# xiao_mx.net
KiCad netlist of a schematic drawn in EAGLE
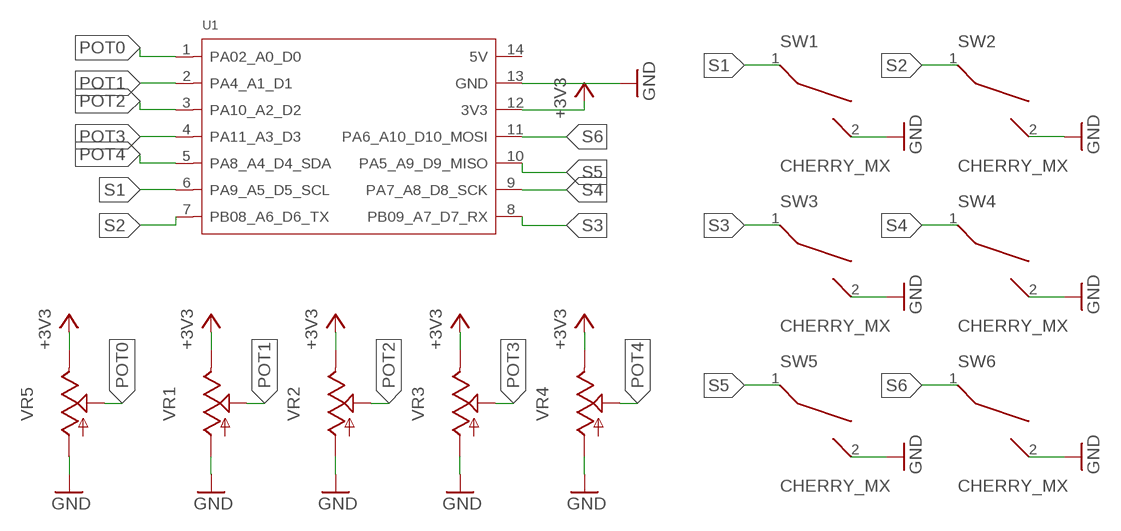
[diagram p0: schematic, sheet 1]

(export (version "E")
  (design (tool "Eeschema 10.0.6"))
  (components
    (comp (ref "SW1")
      (value "CHERRY_MX")
      (footprint "eagle-import:MX1A-XXNN")
      (libsource (lib "eagle-import") (part "CHERRY_MX"))
    )
    (comp (ref "SW2")
      (value "CHERRY_MX")
      (footprint "eagle-import:MX1A-XXNN")
      (libsource (lib "eagle-import") (part "CHERRY_MX"))
    )
    (comp (ref "SW3")
      (value "CHERRY_MX")
      (footprint "eagle-import:MX1A-XXNN")
      (libsource (lib "eagle-import") (part "CHERRY_MX"))
    )
    (comp (ref "SW4")
      (value "CHERRY_MX")
      (footprint "eagle-import:MX1A-XXNN")
      (libsource (lib "eagle-import") (part "CHERRY_MX"))
    )
    (comp (ref "SW5")
      (value "CHERRY_MX")
      (footprint "eagle-import:MX1A-XXNN")
      (libsource (lib "eagle-import") (part "CHERRY_MX"))
    )
    (comp (ref "SW6")
      (value "CHERRY_MX")
      (footprint "eagle-import:MX1A-XXNN")
      (libsource (lib "eagle-import") (part "CHERRY_MX"))
    )
    (comp (ref "U1")
      (value "MOUDLE-SEEEDUINO-XIAO")
      (footprint "eagle-import:MOUDLE14P-2.54-21X17.8MM")
      (libsource (lib "eagle-import") (part "MOUDLE-SEEEDUINO-XIAO"))
    )
    (comp (ref "VR1")
      (value "9MM_SNAP-IN_POT_")
      (footprint "eagle-import:9MM_SNAP-IN_POT")
      (libsource (lib "eagle-import") (part "9MM_SNAP-IN_POT_"))
    )
    (comp (ref "VR2")
      (value "9MM_SNAP-IN_POT_")
      (footprint "eagle-import:9MM_SNAP-IN_POT")
      (libsource (lib "eagle-import") (part "9MM_SNAP-IN_POT_"))
    )
    (comp (ref "VR3")
      (value "9MM_SNAP-IN_POT_")
      (footprint "eagle-import:9MM_SNAP-IN_POT")
      (libsource (lib "eagle-import") (part "9MM_SNAP-IN_POT_"))
    )
    (comp (ref "VR4")
      (value "9MM_SNAP-IN_POT_")
      (footprint "eagle-import:9MM_SNAP-IN_POT")
      (libsource (lib "eagle-import") (part "9MM_SNAP-IN_POT_"))
    )
    (comp (ref "VR5")
      (value "9MM_SNAP-IN_POT_")
      (footprint "eagle-import:9MM_SNAP-IN_POT")
      (libsource (lib "eagle-import") (part "9MM_SNAP-IN_POT_"))
    )
  )
  (nets
    (net (code "1") (name "+3V3") (class "Default")
      (node (ref "U1") (pin "12") (pinfunction "3V3_12") (pintype "bidirectional"))
      (node (ref "VR1") (pin "3") (pinfunction "E_3") (pintype "passive"))
      (node (ref "VR2") (pin "3") (pinfunction "E_3") (pintype "passive"))
      (node (ref "VR3") (pin "3") (pinfunction "E_3") (pintype "passive"))
      (node (ref "VR4") (pin "3") (pinfunction "E_3") (pintype "passive"))
      (node (ref "VR5") (pin "3") (pinfunction "E_3") (pintype "passive"))
    )
    (net (code "2") (name "GND") (class "Default")
      (node (ref "SW1") (pin "2") (pinfunction "2_2") (pintype "passive"))
      (node (ref "SW2") (pin "2") (pinfunction "2_2") (pintype "passive"))
      (node (ref "SW3") (pin "2") (pinfunction "2_2") (pintype "passive"))
      (node (ref "SW4") (pin "2") (pinfunction "2_2") (pintype "passive"))
      (node (ref "SW5") (pin "2") (pinfunction "2_2") (pintype "passive"))
      (node (ref "SW6") (pin "2") (pinfunction "2_2") (pintype "passive"))
      (node (ref "U1") (pin "13") (pinfunction "GND_13") (pintype "bidirectional"))
      (node (ref "VR1") (pin "1") (pinfunction "A_1") (pintype "passive"))
      (node (ref "VR2") (pin "1") (pinfunction "A_1") (pintype "passive"))
      (node (ref "VR3") (pin "1") (pinfunction "A_1") (pintype "passive"))
      (node (ref "VR4") (pin "1") (pinfunction "A_1") (pintype "passive"))
      (node (ref "VR5") (pin "1") (pinfunction "A_1") (pintype "passive"))
    )
    (net (code "3") (name "POT0") (class "Default")
      (node (ref "U1") (pin "1") (pinfunction "PA02_A0_D0_1") (pintype "bidirectional"))
      (node (ref "VR5") (pin "2") (pinfunction "S_2") (pintype "passive"))
    )
    (net (code "4") (name "POT1") (class "Default")
      (node (ref "U1") (pin "2") (pinfunction "PA4_A1_D1_2") (pintype "bidirectional"))
      (node (ref "VR1") (pin "2") (pinfunction "S_2") (pintype "passive"))
    )
    (net (code "5") (name "POT2") (class "Default")
      (node (ref "U1") (pin "3") (pinfunction "PA10_A2_D2_3") (pintype "bidirectional"))
      (node (ref "VR2") (pin "2") (pinfunction "S_2") (pintype "passive"))
    )
    (net (code "6") (name "POT3") (class "Default")
      (node (ref "U1") (pin "4") (pinfunction "PA11_A3_D3_4") (pintype "bidirectional"))
      (node (ref "VR3") (pin "2") (pinfunction "S_2") (pintype "passive"))
    )
    (net (code "7") (name "POT4") (class "Default")
      (node (ref "U1") (pin "5") (pinfunction "PA8_A4_D4_SDA_5") (pintype "bidirectional"))
      (node (ref "VR4") (pin "2") (pinfunction "S_2") (pintype "passive"))
    )
    (net (code "8") (name "S1") (class "Default")
      (node (ref "SW1") (pin "1") (pinfunction "1_1") (pintype "passive"))
      (node (ref "U1") (pin "6") (pinfunction "PA9_A5_D5_SCL_6") (pintype "bidirectional"))
    )
    (net (code "9") (name "S2") (class "Default")
      (node (ref "SW2") (pin "1") (pinfunction "1_1") (pintype "passive"))
      (node (ref "U1") (pin "7") (pinfunction "PB08_A6_D6_TX_7") (pintype "bidirectional"))
    )
    (net (code "10") (name "S3") (class "Default")
      (node (ref "SW3") (pin "1") (pinfunction "1_1") (pintype "passive"))
      (node (ref "U1") (pin "8") (pinfunction "PB09_A7_D7_RX_8") (pintype "bidirectional"))
    )
    (net (code "11") (name "S4") (class "Default")
      (node (ref "SW4") (pin "1") (pinfunction "1_1") (pintype "passive"))
      (node (ref "U1") (pin "9") (pinfunction "PA7_A8_D8_SCK_9") (pintype "bidirectional"))
    )
    (net (code "12") (name "S5") (class "Default")
      (node (ref "SW5") (pin "1") (pinfunction "1_1") (pintype "passive"))
      (node (ref "U1") (pin "10") (pinfunction "PA5_A9_D9_MISO_10") (pintype "bidirectional"))
    )
    (net (code "13") (name "S6") (class "Default")
      (node (ref "SW6") (pin "1") (pinfunction "1_1") (pintype "passive"))
      (node (ref "U1") (pin "11") (pinfunction "PA6_A10_D10_MOSI_11") (pintype "bidirectional"))
    )
    (net (code "14") (name "unconnected-(U1-5V-Pad14)") (class "Default")
      (node (ref "U1") (pin "14") (pinfunction "5V_14") (pintype "bidirectional"))
    )
  )
)
